# Schematic-final-Susai-Florian.net
KiCad netlist of a schematic drawn in EAGLE
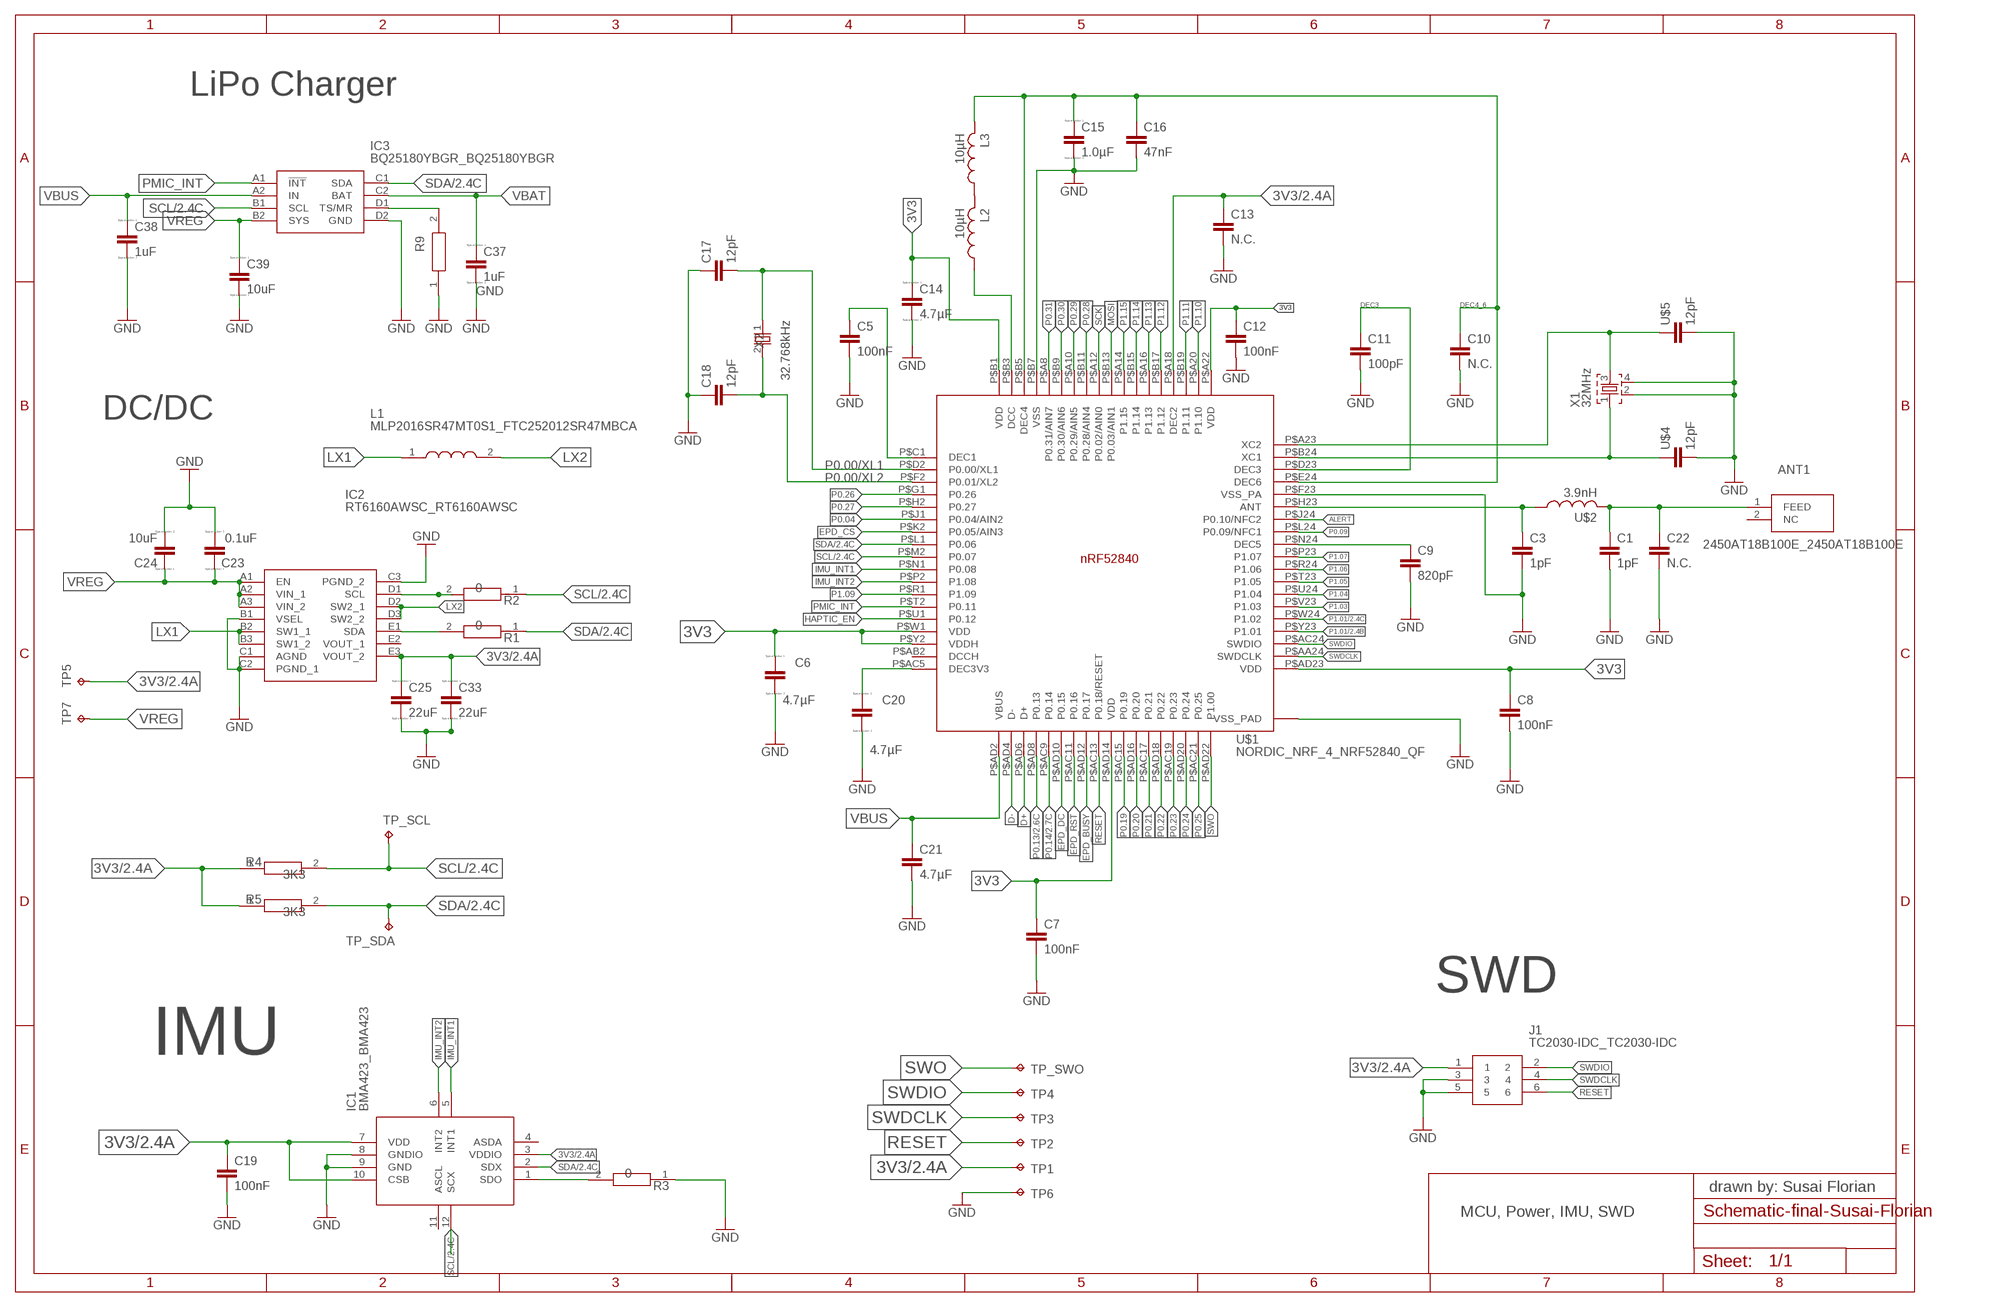
[diagram p0: schematic, sheet 1, part 1 of 2]
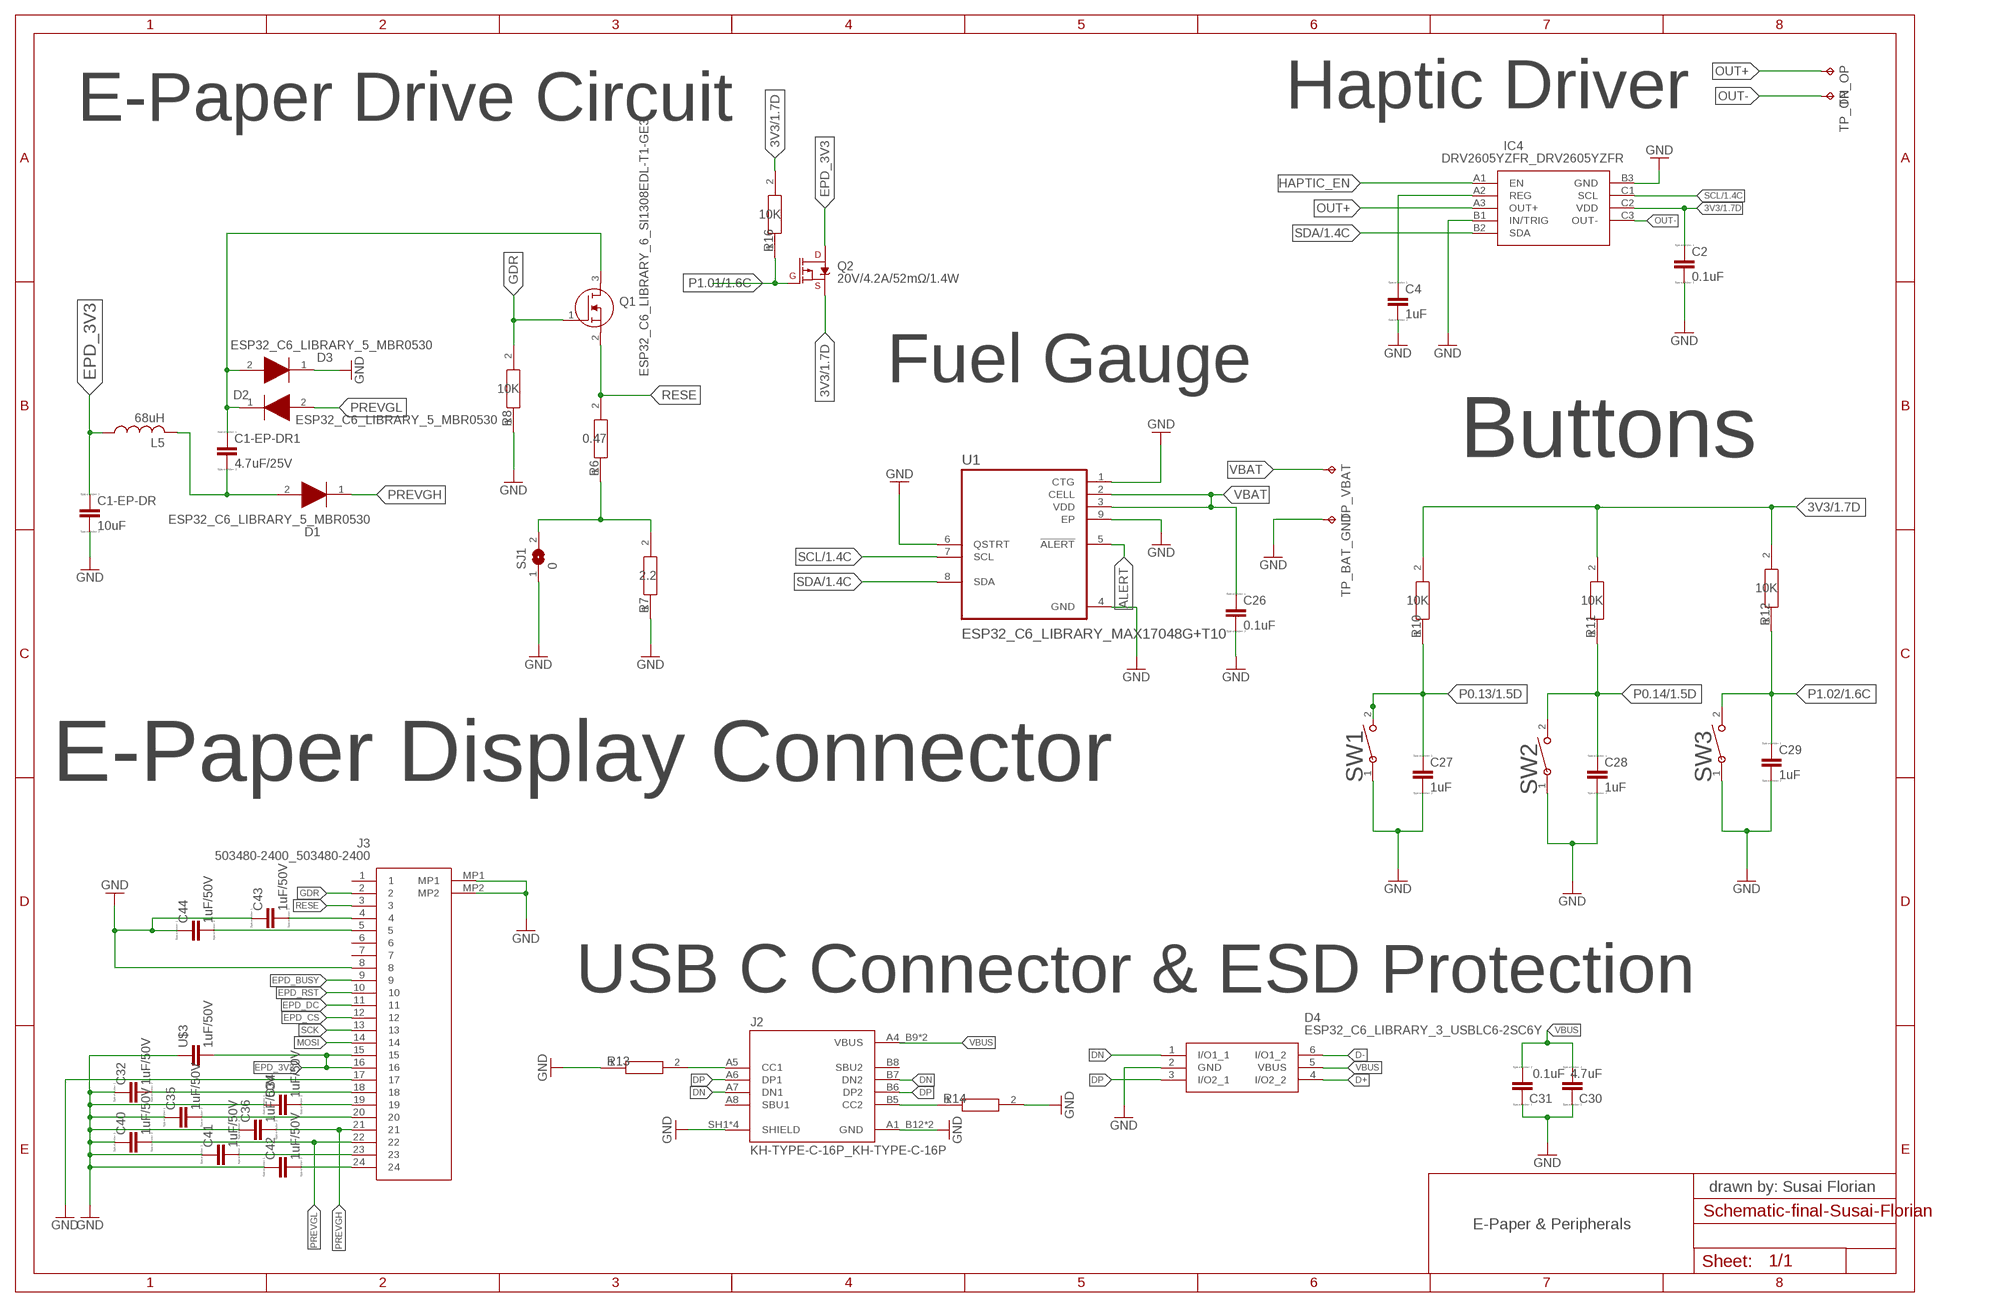
[diagram p1: schematic, sheet 1, part 2 of 2]

(export (version "E")
  (design (tool "Eeschema 10.0.6"))
  (components
    (comp (ref "ANT1")
      (value "2450AT18B100E_2450AT18B100E")
      (footprint "eagle-import:2450AT18B100E_ANTC3216X140N")
      (fields
        (field (name "ARROW_PART_NUMBER") "2450AT18B100E")
        (field (name "MOUSER_PART_NUMBER") "609-2450AT18B100E")
      )
      (libsource (lib "eagle-import") (part "2450AT18B100E_2450AT18B100E"))
    )
    (comp (ref "C1")
      (value "1pF")
      (footprint "eagle-import:NORDIC_NRF_3_RESC0201_L")
      (libsource (lib "eagle-import") (part "NORDIC_NRF_3_CAPACITOR_0201_L"))
    )
    (comp (ref "C1-EP-DR")
      (value "10uF")
      (footprint "eagle-import:ESP32_C6_LIBRARY_1_ESP32_WROVER_EAGLE-LTSPICE_C0402")
      (libsource (lib "eagle-import") (part "ESP32_C6_LIBRARY_1_ESP32_WROVER_EAGLE-LTSPICE_CC0402"))
    )
    (comp (ref "C1-EP-DR1")
      (value "4.7uF/25V")
      (footprint "eagle-import:ESP32_C6_LIBRARY_1_ESP32_WROVER_EAGLE-LTSPICE_C0402")
      (libsource (lib "eagle-import") (part "ESP32_C6_LIBRARY_1_ESP32_WROVER_EAGLE-LTSPICE_CC0402"))
    )
    (comp (ref "C2")
      (value "0.1uF")
      (footprint "eagle-import:ESP32_C6_LIBRARY_1_ESP32_WROVER_EAGLE-LTSPICE_C0402")
      (libsource (lib "eagle-import") (part "ESP32_C6_LIBRARY_1_ESP32_WROVER_EAGLE-LTSPICE_CC0402"))
    )
    (comp (ref "C3")
      (value "1pF")
      (footprint "eagle-import:NORDIC_NRF_3_RESC0201_L")
      (libsource (lib "eagle-import") (part "NORDIC_NRF_3_CAPACITOR_0201_L"))
    )
    (comp (ref "C4")
      (value "1uF")
      (footprint "eagle-import:ESP32_C6_LIBRARY_1_ESP32_WROVER_EAGLE-LTSPICE_C0402")
      (libsource (lib "eagle-import") (part "ESP32_C6_LIBRARY_1_ESP32_WROVER_EAGLE-LTSPICE_CC0402"))
    )
    (comp (ref "C5")
      (value "100nF")
      (footprint "eagle-import:NORDIC_NRF_3_RESC0201_L")
      (libsource (lib "eagle-import") (part "NORDIC_NRF_3_CAPACITOR_0201_L"))
    )
    (comp (ref "C6")
      (value "4.7µF")
      (footprint "eagle-import:ESP32_C6_LIBRARY_1_ESP32_WROVER_EAGLE-LTSPICE_C0402")
      (libsource (lib "eagle-import") (part "ESP32_C6_LIBRARY_1_ESP32_WROVER_EAGLE-LTSPICE_CC0402"))
    )
    (comp (ref "C7")
      (value "100nF")
      (footprint "eagle-import:NORDIC_NRF_3_RESC0201_L")
      (libsource (lib "eagle-import") (part "NORDIC_NRF_3_CAPACITOR_0201_L"))
    )
    (comp (ref "C8")
      (value "100nF")
      (footprint "eagle-import:NORDIC_NRF_3_RESC0201_L")
      (libsource (lib "eagle-import") (part "NORDIC_NRF_3_CAPACITOR_0201_L"))
    )
    (comp (ref "C9")
      (value "820pF")
      (footprint "eagle-import:NORDIC_NRF_3_RESC0201_L")
      (libsource (lib "eagle-import") (part "NORDIC_NRF_3_CAPACITOR_0201_L"))
    )
    (comp (ref "C10")
      (value "N.C.")
      (footprint "eagle-import:NORDIC_NRF_3_RESC0201_L")
      (libsource (lib "eagle-import") (part "NORDIC_NRF_3_CAPACITOR_0201_L"))
    )
    (comp (ref "C11")
      (value "100pF")
      (footprint "eagle-import:NORDIC_NRF_3_RESC0201_L")
      (libsource (lib "eagle-import") (part "NORDIC_NRF_3_CAPACITOR_0201_L"))
    )
    (comp (ref "C12")
      (value "100nF")
      (footprint "eagle-import:NORDIC_NRF_3_RESC0201_L")
      (libsource (lib "eagle-import") (part "NORDIC_NRF_3_CAPACITOR_0201_L"))
    )
    (comp (ref "C13")
      (value "N.C.")
      (footprint "eagle-import:NORDIC_NRF_3_RESC0201_L")
      (libsource (lib "eagle-import") (part "NORDIC_NRF_3_CAPACITOR_0201_L"))
    )
    (comp (ref "C14")
      (value "4.7µF")
      (footprint "eagle-import:ESP32_C6_LIBRARY_1_ESP32_WROVER_EAGLE-LTSPICE_C0402")
      (libsource (lib "eagle-import") (part "ESP32_C6_LIBRARY_1_ESP32_WROVER_EAGLE-LTSPICE_CC0402"))
    )
    (comp (ref "C15")
      (value "1.0µF")
      (footprint "eagle-import:ESP32_C6_LIBRARY_1_ESP32_WROVER_EAGLE-LTSPICE_C0402")
      (libsource (lib "eagle-import") (part "ESP32_C6_LIBRARY_1_ESP32_WROVER_EAGLE-LTSPICE_CC0402"))
    )
    (comp (ref "C16")
      (value "47nF")
      (footprint "eagle-import:NORDIC_NRF_3_RESC0201_L")
      (libsource (lib "eagle-import") (part "NORDIC_NRF_3_CAPACITOR_0201_L"))
    )
    (comp (ref "C17")
      (value "12pF")
      (footprint "eagle-import:NORDIC_NRF_3_RESC0201_L")
      (libsource (lib "eagle-import") (part "NORDIC_NRF_3_CAPACITOR_0201_L"))
    )
    (comp (ref "C18")
      (value "12pF")
      (footprint "eagle-import:NORDIC_NRF_3_RESC0201_L")
      (libsource (lib "eagle-import") (part "NORDIC_NRF_3_CAPACITOR_0201_L"))
    )
    (comp (ref "C19")
      (value "100nF")
      (footprint "eagle-import:NORDIC_NRF_3_RESC0201_L")
      (libsource (lib "eagle-import") (part "NORDIC_NRF_3_CAPACITOR_0201_L"))
    )
    (comp (ref "C20")
      (value "4.7µF")
      (footprint "eagle-import:ESP32_C6_LIBRARY_1_ESP32_WROVER_EAGLE-LTSPICE_C0402")
      (libsource (lib "eagle-import") (part "ESP32_C6_LIBRARY_1_ESP32_WROVER_EAGLE-LTSPICE_CC0402"))
    )
    (comp (ref "C21")
      (value "4.7µF")
      (footprint "eagle-import:NORDIC_NRF_3_RESC0402_L")
      (libsource (lib "eagle-import") (part "NORDIC_NRF_3_CAPACITOR_0402_L"))
    )
    (comp (ref "C22")
      (value "N.C.")
      (footprint "eagle-import:NORDIC_NRF_3_RESC0201_L")
      (libsource (lib "eagle-import") (part "NORDIC_NRF_3_CAPACITOR_0201_L"))
    )
    (comp (ref "C23")
      (value "0.1uF")
      (footprint "eagle-import:ESP32_C6_LIBRARY_1_ESP32_WROVER_EAGLE-LTSPICE_C0402")
      (libsource (lib "eagle-import") (part "ESP32_C6_LIBRARY_1_ESP32_WROVER_EAGLE-LTSPICE_CC0402"))
    )
    (comp (ref "C24")
      (value "10uF")
      (footprint "eagle-import:ESP32_C6_LIBRARY_1_ESP32_WROVER_EAGLE-LTSPICE_C0402")
      (libsource (lib "eagle-import") (part "ESP32_C6_LIBRARY_1_ESP32_WROVER_EAGLE-LTSPICE_CC0402"))
    )
    (comp (ref "C25")
      (value "22uF")
      (footprint "eagle-import:ESP32_C6_LIBRARY_1_ESP32_WROVER_EAGLE-LTSPICE_C0402")
      (libsource (lib "eagle-import") (part "ESP32_C6_LIBRARY_1_ESP32_WROVER_EAGLE-LTSPICE_CC0402"))
    )
    (comp (ref "C26")
      (value "0.1uF")
      (footprint "eagle-import:ESP32_C6_LIBRARY_1_ESP32_WROVER_EAGLE-LTSPICE_C0402")
      (libsource (lib "eagle-import") (part "ESP32_C6_LIBRARY_1_ESP32_WROVER_EAGLE-LTSPICE_CC0402"))
    )
    (comp (ref "C27")
      (value "1uF")
      (footprint "eagle-import:ESP32_C6_LIBRARY_1_ESP32_WROVER_EAGLE-LTSPICE_C0402")
      (libsource (lib "eagle-import") (part "ESP32_C6_LIBRARY_1_ESP32_WROVER_EAGLE-LTSPICE_CC0402"))
    )
    (comp (ref "C28")
      (value "1uF")
      (footprint "eagle-import:ESP32_C6_LIBRARY_1_ESP32_WROVER_EAGLE-LTSPICE_C0402")
      (libsource (lib "eagle-import") (part "ESP32_C6_LIBRARY_1_ESP32_WROVER_EAGLE-LTSPICE_CC0402"))
    )
    (comp (ref "C29")
      (value "1uF")
      (footprint "eagle-import:ESP32_C6_LIBRARY_1_ESP32_WROVER_EAGLE-LTSPICE_C0402")
      (libsource (lib "eagle-import") (part "ESP32_C6_LIBRARY_1_ESP32_WROVER_EAGLE-LTSPICE_CC0402"))
    )
    (comp (ref "C30")
      (value "4.7uF")
      (footprint "eagle-import:ESP32_C6_LIBRARY_1_ESP32_WROVER_EAGLE-LTSPICE_C0402")
      (libsource (lib "eagle-import") (part "ESP32_C6_LIBRARY_1_ESP32_WROVER_EAGLE-LTSPICE_CC0402"))
    )
    (comp (ref "C31")
      (value "0.1uF")
      (footprint "eagle-import:ESP32_C6_LIBRARY_1_ESP32_WROVER_EAGLE-LTSPICE_C0402")
      (libsource (lib "eagle-import") (part "ESP32_C6_LIBRARY_1_ESP32_WROVER_EAGLE-LTSPICE_CC0402"))
    )
    (comp (ref "C32")
      (value "1uF/50V")
      (footprint "eagle-import:ESP32_C6_LIBRARY_1_ESP32_WROVER_EAGLE-LTSPICE_C0402")
      (libsource (lib "eagle-import") (part "ESP32_C6_LIBRARY_1_ESP32_WROVER_EAGLE-LTSPICE_CC0402"))
    )
    (comp (ref "C33")
      (value "22uF")
      (footprint "eagle-import:ESP32_C6_LIBRARY_1_ESP32_WROVER_EAGLE-LTSPICE_C0402")
      (libsource (lib "eagle-import") (part "ESP32_C6_LIBRARY_1_ESP32_WROVER_EAGLE-LTSPICE_CC0402"))
    )
    (comp (ref "C34")
      (value "1uF/50V")
      (footprint "eagle-import:ESP32_C6_LIBRARY_1_ESP32_WROVER_EAGLE-LTSPICE_C0402")
      (libsource (lib "eagle-import") (part "ESP32_C6_LIBRARY_1_ESP32_WROVER_EAGLE-LTSPICE_CC0402"))
    )
    (comp (ref "C35")
      (value "1uF/50V")
      (footprint "eagle-import:ESP32_C6_LIBRARY_1_ESP32_WROVER_EAGLE-LTSPICE_C0402")
      (libsource (lib "eagle-import") (part "ESP32_C6_LIBRARY_1_ESP32_WROVER_EAGLE-LTSPICE_CC0402"))
    )
    (comp (ref "C36")
      (value "1uF/50V")
      (footprint "eagle-import:ESP32_C6_LIBRARY_1_ESP32_WROVER_EAGLE-LTSPICE_C0402")
      (libsource (lib "eagle-import") (part "ESP32_C6_LIBRARY_1_ESP32_WROVER_EAGLE-LTSPICE_CC0402"))
    )
    (comp (ref "C37")
      (value "1uF")
      (footprint "eagle-import:ESP32_C6_LIBRARY_1_ESP32_WROVER_EAGLE-LTSPICE_C0402")
      (libsource (lib "eagle-import") (part "ESP32_C6_LIBRARY_1_ESP32_WROVER_EAGLE-LTSPICE_CC0402"))
    )
    (comp (ref "C38")
      (value "1uF")
      (footprint "eagle-import:ESP32_C6_LIBRARY_1_ESP32_WROVER_EAGLE-LTSPICE_C0402")
      (libsource (lib "eagle-import") (part "ESP32_C6_LIBRARY_1_ESP32_WROVER_EAGLE-LTSPICE_CC0402"))
    )
    (comp (ref "C39")
      (value "10uF")
      (footprint "eagle-import:ESP32_C6_LIBRARY_1_ESP32_WROVER_EAGLE-LTSPICE_C0402")
      (libsource (lib "eagle-import") (part "ESP32_C6_LIBRARY_1_ESP32_WROVER_EAGLE-LTSPICE_CC0402"))
    )
    (comp (ref "C40")
      (value "1uF/50V")
      (footprint "eagle-import:ESP32_C6_LIBRARY_1_ESP32_WROVER_EAGLE-LTSPICE_C0402")
      (libsource (lib "eagle-import") (part "ESP32_C6_LIBRARY_1_ESP32_WROVER_EAGLE-LTSPICE_CC0402"))
    )
    (comp (ref "C41")
      (value "1uF/50V")
      (footprint "eagle-import:ESP32_C6_LIBRARY_1_ESP32_WROVER_EAGLE-LTSPICE_C0402")
      (libsource (lib "eagle-import") (part "ESP32_C6_LIBRARY_1_ESP32_WROVER_EAGLE-LTSPICE_CC0402"))
    )
    (comp (ref "C42")
      (value "1uF/50V")
      (footprint "eagle-import:ESP32_C6_LIBRARY_1_ESP32_WROVER_EAGLE-LTSPICE_C0402")
      (libsource (lib "eagle-import") (part "ESP32_C6_LIBRARY_1_ESP32_WROVER_EAGLE-LTSPICE_CC0402"))
    )
    (comp (ref "C43")
      (value "1uF/50V")
      (footprint "eagle-import:ESP32_C6_LIBRARY_1_ESP32_WROVER_EAGLE-LTSPICE_C0402")
      (libsource (lib "eagle-import") (part "ESP32_C6_LIBRARY_1_ESP32_WROVER_EAGLE-LTSPICE_CC0402"))
    )
    (comp (ref "C44")
      (value "1uF/50V")
      (footprint "eagle-import:ESP32_C6_LIBRARY_1_ESP32_WROVER_EAGLE-LTSPICE_C0402")
      (libsource (lib "eagle-import") (part "ESP32_C6_LIBRARY_1_ESP32_WROVER_EAGLE-LTSPICE_CC0402"))
    )
    (comp (ref "D1")
      (value "ESP32_C6_LIBRARY_5_MBR0530")
      (footprint "eagle-import:ESP32_C6_LIBRARY_5_SOD3716X135N")
      (fields (field (name "MF") "ON Semiconductor") (field (name "MP") "MBR0530"))
      (libsource (lib "eagle-import") (part "ESP32_C6_LIBRARY_5_MBR0530"))
    )
    (comp (ref "D2")
      (value "ESP32_C6_LIBRARY_5_MBR0530")
      (footprint "eagle-import:ESP32_C6_LIBRARY_5_SOD3716X135N")
      (fields (field (name "MF") "ON Semiconductor") (field (name "MP") "MBR0530"))
      (libsource (lib "eagle-import") (part "ESP32_C6_LIBRARY_5_MBR0530"))
    )
    (comp (ref "D3")
      (value "ESP32_C6_LIBRARY_5_MBR0530")
      (footprint "eagle-import:ESP32_C6_LIBRARY_5_SOD3716X135N")
      (fields (field (name "MF") "ON Semiconductor") (field (name "MP") "MBR0530"))
      (libsource (lib "eagle-import") (part "ESP32_C6_LIBRARY_5_MBR0530"))
    )
    (comp (ref "D4")
      (value "ESP32_C6_LIBRARY_3_USBLC6-2SC6Y")
      (footprint "eagle-import:ESP32_C6_LIBRARY_3_SOT95P280X145-6N")
      (fields (field (name "MF") "STMicroelectronics") (field (name "MP") "USBLC6-2SC6Y"))
      (libsource (lib "eagle-import") (part "ESP32_C6_LIBRARY_3_USBLC6-2SC6Y"))
    )
    (comp (ref "IC1")
      (value "BMA423_BMA423")
      (footprint "eagle-import:BMA423_BMA423")
      (fields (field (name "ARROW_PART_NUMBER") "BMA423") (field (name "MOUSER_PART_NUMBER") "262-BMA423"))
      (libsource (lib "eagle-import") (part "BMA423_BMA423"))
    )
    (comp (ref "IC2")
      (value "RT6160AWSC_RT6160AWSC")
      (footprint "eagle-import:RT6160AWSC_BGA15C40P3X5_140X230X60")
      (fields
        (field (name "MANUFACTURER_PART_NUMBER") "RT6160AWSC")
        (field (name "MOUSER_PART_NUMBER") "835-RT6160AWSC")
      )
      (libsource (lib "eagle-import") (part "RT6160AWSC_RT6160AWSC"))
    )
    (comp (ref "IC3")
      (value "BQ25180YBGR_BQ25180YBGR")
      (footprint "eagle-import:BQ25180YBGR_BGA8C40P2X4_100X155X50")
      (fields
        (field (name "ARROW_PART_NUMBER") "BQ25180YBGR")
        (field (name "MOUSER_PART_NUMBER") "595-BQ25180YBGR")
      )
      (libsource (lib "eagle-import") (part "BQ25180YBGR_BQ25180YBGR"))
    )
    (comp (ref "IC4")
      (value "DRV2605YZFR_DRV2605YZFR")
      (footprint "eagle-import:DRV2605YZFR_BGA9C50P3X3_144X144X62")
      (fields (field (name "ARROW_PART_NUMBER") "DRV2605YZFR"))
      (libsource (lib "eagle-import") (part "DRV2605YZFR_DRV2605YZFR"))
    )
    (comp (ref "J1")
      (value "TC2030-IDC_TC2030-IDC")
      (footprint "eagle-import:TC2030-IDC_TC2030IDC")
      (fields (field (name "MANUFACTURER_PART_NUMBER") "TC2030-IDC"))
      (libsource (lib "eagle-import") (part "TC2030-IDC_TC2030-IDC"))
    )
    (comp (ref "J2")
      (value "KH-TYPE-C-16P_KH-TYPE-C-16P")
      (footprint "eagle-import:KH-TYPE-C-16P_KINGHELM_KH-TYPE-C-16P")
      (fields (field (name "MF") "kinghelm") (field (name "MP") "KH-TYPE-C-16P"))
      (libsource (lib "eagle-import") (part "KH-TYPE-C-16P_KH-TYPE-C-16P"))
    )
    (comp (ref "J3")
      (value "503480-2400_503480-2400")
      (footprint "eagle-import:503480-2400_5034802400")
      (fields
        (field (name "MANUFACTURER_PART_NUMBER") "503480-2400")
        (field (name "MOUSER_PART_NUMBER") "538-503480-2400")
      )
      (libsource (lib "eagle-import") (part "503480-2400_503480-2400"))
    )
    (comp (ref "L1")
      (value "MLP2016SR47MT0S1_FTC252012SR47MBCA")
      (footprint "eagle-import:MLP2016SR47MT0S1_INDC2016X100N")
      (fields (field (name "MANUFACTURER_PART_NUMBER") "FTC252012SR47MBCA"))
      (libsource (lib "eagle-import") (part "MLP2016SR47MT0S1_FTC252012SR47MBCA"))
    )
    (comp (ref "L2")
      (value "10µH")
      (footprint "eagle-import:NORDIC_NRF_2_RESC0402_L")
      (libsource (lib "eagle-import") (part "NORDIC_NRF_2_INDUCTOR_0402_L"))
    )
    (comp (ref "L3")
      (value "10µH")
      (footprint "eagle-import:NORDIC_NRF_2_RESC0402_L")
      (libsource (lib "eagle-import") (part "NORDIC_NRF_2_INDUCTOR_0402_L"))
    )
    (comp (ref "L5")
      (value "68uH")
      (footprint "eagle-import:NORDIC_NRF_2_RESC0201_L")
      (libsource (lib "eagle-import") (part "NORDIC_NRF_2_INDUCTOR_0201_L"))
    )
    (comp (ref "Q1")
      (value "ESP32_C6_LIBRARY_6_SI1308EDL-T1-GE3")
      (footprint "eagle-import:ESP32_C6_LIBRARY_6_SOT65P210X110-3N")
      (fields (field (name "MF") "Vishay Siliconix") (field (name "MP") "SI1308EDL-T1-GE3"))
      (libsource (lib "eagle-import") (part "ESP32_C6_LIBRARY_6_SI1308EDL-T1-GE3"))
    )
    (comp (ref "Q2")
      (value "20V/4.2A/52mΩ/1.4W")
      (footprint "eagle-import:ESP32_C6_LIBRARY_4_ESP32_C6_LIBRARY_4_ESP32_C6_LIBRARY_4_ESP32_C6_LIBRARY_4_ESP32_WROVER_SPARKFUN-DISCRETESEMI_SOT23-3")
      (libsource (lib "eagle-import") (part "ESP32_C6_LIBRARY_4_ESP32_WROVER_SPARKFUN-DISCRETESEMI_MOSFET_PCH-DMG2305UX-7"))
    )
    (comp (ref "R1")
      (value "0")
      (footprint "eagle-import:CPF0201D7K68C1_0201")
      (libsource (lib "eagle-import") (part "CPF0201D7K68C1_CPF0201D7K68C1"))
    )
    (comp (ref "R2")
      (value "0")
      (footprint "eagle-import:CPF0201D7K68C1_0201")
      (libsource (lib "eagle-import") (part "CPF0201D7K68C1_CPF0201D7K68C1"))
    )
    (comp (ref "R3")
      (value "0")
      (footprint "eagle-import:CPF0201D7K68C1_0201")
      (libsource (lib "eagle-import") (part "CPF0201D7K68C1_CPF0201D7K68C1"))
    )
    (comp (ref "R4")
      (value "3K3")
      (footprint "eagle-import:CPF0201D7K68C1_0201")
      (libsource (lib "eagle-import") (part "CPF0201D7K68C1_CPF0201D7K68C1"))
    )
    (comp (ref "R5")
      (value "3K3")
      (footprint "eagle-import:CPF0201D7K68C1_0201")
      (libsource (lib "eagle-import") (part "CPF0201D7K68C1_CPF0201D7K68C1"))
    )
    (comp (ref "R6")
      (value "0.47")
      (footprint "eagle-import:CPF0201D7K68C1_0201")
      (libsource (lib "eagle-import") (part "CPF0201D7K68C1_CPF0201D7K68C1"))
    )
    (comp (ref "R7")
      (value "2.2")
      (footprint "eagle-import:CPF0201D7K68C1_0201")
      (libsource (lib "eagle-import") (part "CPF0201D7K68C1_CPF0201D7K68C1"))
    )
    (comp (ref "R8")
      (value "10K")
      (footprint "eagle-import:CPF0201D7K68C1_0201")
      (libsource (lib "eagle-import") (part "CPF0201D7K68C1_CPF0201D7K68C1"))
    )
    (comp (ref "R9")
      (value "10K")
      (footprint "eagle-import:CPF0201D7K68C1_0201")
      (libsource (lib "eagle-import") (part "CPF0201D7K68C1_CPF0201D7K68C1"))
    )
    (comp (ref "R10")
      (value "10K")
      (footprint "eagle-import:CPF0201D7K68C1_0201")
      (libsource (lib "eagle-import") (part "CPF0201D7K68C1_CPF0201D7K68C1"))
    )
    (comp (ref "R11")
      (value "10K")
      (footprint "eagle-import:CPF0201D7K68C1_0201")
      (libsource (lib "eagle-import") (part "CPF0201D7K68C1_CPF0201D7K68C1"))
    )
    (comp (ref "R12")
      (value "10K")
      (footprint "eagle-import:CPF0201D7K68C1_0201")
      (libsource (lib "eagle-import") (part "CPF0201D7K68C1_CPF0201D7K68C1"))
    )
    (comp (ref "R13")
      (value "10K")
      (footprint "eagle-import:CPF0201D7K68C1_0201")
      (libsource (lib "eagle-import") (part "CPF0201D7K68C1_CPF0201D7K68C1"))
    )
    (comp (ref "R14")
      (value "10K")
      (footprint "eagle-import:CPF0201D7K68C1_0201")
      (libsource (lib "eagle-import") (part "CPF0201D7K68C1_CPF0201D7K68C1"))
    )
    (comp (ref "R16")
      (value "10K")
      (footprint "eagle-import:CPF0201D7K68C1_0201")
      (libsource (lib "eagle-import") (part "CPF0201D7K68C1_CPF0201D7K68C1"))
    )
    (comp (ref "SJ1")
      (value "0")
      (footprint "eagle-import:ESP32_C6_LIBRARY_7_JUMPER_SJ")
      (libsource (lib "eagle-import") (part "ESP32_C6_LIBRARY_7_JUMPER_SJ"))
    )
    (comp (ref "SW1")
      (value "2025-10-22_07-23-44_LIBRARY_EVP-AKE31ASW_EVP-AKE31A_PAN")
      (footprint "eagle-import:2025-10-22_07-23-44_LIBRARY_SW_EVP-AKE31A_PAN")
      (fields
        (field (name "MANUFACTURER_PART_NUMBER") "EVP-AKE31A")
        (field (name "COPYRIGHT") "Copyright (C) 2025 Ultra Librarian. All rights reserved.")
      )
      (libsource (lib "eagle-import") (part "2025-10-22_07-23-44_LIBRARY_EVP-AKE31ASW_EVP-AKE31A_PAN"))
    )
    (comp (ref "SW2")
      (value "2025-10-22_07-23-44_LIBRARY_EVP-AKE31ASW_EVP-AKE31A_PAN")
      (footprint "eagle-import:2025-10-22_07-23-44_LIBRARY_SW_EVP-AKE31A_PAN")
      (fields
        (field (name "MANUFACTURER_PART_NUMBER") "EVP-AKE31A")
        (field (name "COPYRIGHT") "Copyright (C) 2025 Ultra Librarian. All rights reserved.")
      )
      (libsource (lib "eagle-import") (part "2025-10-22_07-23-44_LIBRARY_EVP-AKE31ASW_EVP-AKE31A_PAN"))
    )
    (comp (ref "SW3")
      (value "2025-10-22_07-23-44_LIBRARY_EVP-AKE31ASW_EVP-AKE31A_PAN")
      (footprint "eagle-import:2025-10-22_07-23-44_LIBRARY_SW_EVP-AKE31A_PAN")
      (fields
        (field (name "MANUFACTURER_PART_NUMBER") "EVP-AKE31A")
        (field (name "COPYRIGHT") "Copyright (C) 2025 Ultra Librarian. All rights reserved.")
      )
      (libsource (lib "eagle-import") (part "2025-10-22_07-23-44_LIBRARY_EVP-AKE31ASW_EVP-AKE31A_PAN"))
    )
    (comp (ref "TP1")
      (value "HECTOR_WATCH_1_TPTP20R")
      (footprint "eagle-import:HECTOR_WATCH_1_TP20R")
      (libsource (lib "eagle-import") (part "HECTOR_WATCH_1_TPTP20R"))
    )
    (comp (ref "TP2")
      (value "HECTOR_WATCH_1_TPTP20R")
      (footprint "eagle-import:HECTOR_WATCH_1_TP20R")
      (libsource (lib "eagle-import") (part "HECTOR_WATCH_1_TPTP20R"))
    )
    (comp (ref "TP3")
      (value "HECTOR_WATCH_1_TPTP20R")
      (footprint "eagle-import:HECTOR_WATCH_1_TP20R")
      (libsource (lib "eagle-import") (part "HECTOR_WATCH_1_TPTP20R"))
    )
    (comp (ref "TP4")
      (value "HECTOR_WATCH_1_TPTP20R")
      (footprint "eagle-import:HECTOR_WATCH_1_TP20R")
      (libsource (lib "eagle-import") (part "HECTOR_WATCH_1_TPTP20R"))
    )
    (comp (ref "TP5")
      (value "HECTOR_WATCH_1_TPTP20R")
      (footprint "eagle-import:HECTOR_WATCH_1_TP20R")
      (libsource (lib "eagle-import") (part "HECTOR_WATCH_1_TPTP20R"))
    )
    (comp (ref "TP6")
      (value "HECTOR_WATCH_1_TPTP20R")
      (footprint "eagle-import:HECTOR_WATCH_1_TP20R")
      (libsource (lib "eagle-import") (part "HECTOR_WATCH_1_TPTP20R"))
    )
    (comp (ref "TP7")
      (value "HECTOR_WATCH_1_TPTP20R")
      (footprint "eagle-import:HECTOR_WATCH_1_TP20R")
      (libsource (lib "eagle-import") (part "HECTOR_WATCH_1_TPTP20R"))
    )
    (comp (ref "TP_BAT_GND")
      (value "HECTOR_WATCH_1_TPTP20R")
      (footprint "eagle-import:HECTOR_WATCH_1_TP20R")
      (libsource (lib "eagle-import") (part "HECTOR_WATCH_1_TPTP20R"))
    )
    (comp (ref "TP_ON")
      (value "HECTOR_WATCH_1_TPTP20R")
      (footprint "eagle-import:HECTOR_WATCH_1_TP20R")
      (libsource (lib "eagle-import") (part "HECTOR_WATCH_1_TPTP20R"))
    )
    (comp (ref "TP_OP")
      (value "HECTOR_WATCH_1_TPTP20R")
      (footprint "eagle-import:HECTOR_WATCH_1_TP20R")
      (libsource (lib "eagle-import") (part "HECTOR_WATCH_1_TPTP20R"))
    )
    (comp (ref "TP_SCL")
      (value "HECTOR_WATCH_1_TPTP20R")
      (footprint "eagle-import:HECTOR_WATCH_1_TP20R")
      (libsource (lib "eagle-import") (part "HECTOR_WATCH_1_TPTP20R"))
    )
    (comp (ref "TP_SDA")
      (value "HECTOR_WATCH_1_TPTP20R")
      (footprint "eagle-import:HECTOR_WATCH_1_TP20R")
      (libsource (lib "eagle-import") (part "HECTOR_WATCH_1_TPTP20R"))
    )
    (comp (ref "TP_SWO")
      (value "HECTOR_WATCH_1_TPTP20R")
      (footprint "eagle-import:HECTOR_WATCH_1_TP20R")
      (libsource (lib "eagle-import") (part "HECTOR_WATCH_1_TPTP20R"))
    )
    (comp (ref "TP_VBAT")
      (value "HECTOR_WATCH_1_TPTP20R")
      (footprint "eagle-import:HECTOR_WATCH_1_TP20R")
      (libsource (lib "eagle-import") (part "HECTOR_WATCH_1_TPTP20R"))
    )
    (comp (ref "U$1")
      (value "NORDIC_NRF_4_NRF52840_QF")
      (footprint "eagle-import:NORDIC_NRF_4_AQFN50P700X700X85_HS-74N")
      (libsource (lib "eagle-import") (part "NORDIC_NRF_4_NRF52840_QF"))
    )
    (comp (ref "U$2")
      (value "3.9nH")
      (footprint "eagle-import:NORDIC_NRF_2_RESC0402_L")
      (libsource (lib "eagle-import") (part "NORDIC_NRF_2_INDUCTOR_0402_L"))
    )
    (comp (ref "U$3")
      (value "1uF/50V")
      (footprint "eagle-import:NORDIC_NRF_3_RESC0201_L")
      (libsource (lib "eagle-import") (part "NORDIC_NRF_3_CAPACITOR_0201_L"))
    )
    (comp (ref "U$4")
      (value "12pF")
      (footprint "eagle-import:NORDIC_NRF_3_RESC0201_L")
      (libsource (lib "eagle-import") (part "NORDIC_NRF_3_CAPACITOR_0201_L"))
    )
    (comp (ref "U$5")
      (value "12pF")
      (footprint "eagle-import:NORDIC_NRF_3_RESC0201_L")
      (libsource (lib "eagle-import") (part "NORDIC_NRF_3_CAPACITOR_0201_L"))
    )
    (comp (ref "U1")
      (value "ESP32_C6_LIBRARY_MAX17048G+T10")
      (footprint "eagle-import:ESP32_C6_LIBRARY_SON50P200X200X80-9N")
      (fields (field (name "MF") "Analog Devices") (field (name "MP") "MAX17048G+T10"))
      (libsource (lib "eagle-import") (part "ESP32_C6_LIBRARY_MAX17048G+T10"))
    )
    (comp (ref "X1")
      (value "32MHz")
      (footprint "eagle-import:NORDIC_NRF_BT-XTAL_2016_N")
      (libsource (lib "eagle-import") (part "NORDIC_NRF_XTAL_32MHZ"))
    )
    (comp (ref "X2")
      (value "32.768kHz")
      (footprint "eagle-import:NORDIC_NRF_1_XTAL_3215_N")
      (libsource (lib "eagle-import") (part "NORDIC_NRF_1_XTAL_32KHZ"))
    )
  )
  (nets
    (net (code "1") (name "/DEC3") (class "Default")
      (node (ref "C11") (pin "1") (pinfunction "1_1") (pintype "passive"))
      (node (ref "U$1") (pin "P$D23") (pinfunction "DEC3_P$D23") (pintype "bidirectional"))
    )
    (net (code "2") (name "/DEC4_6") (class "Default")
      (node (ref "C10") (pin "1") (pinfunction "1_1") (pintype "passive"))
      (node (ref "C15") (pin "1") (pinfunction "1_1") (pintype "passive"))
      (node (ref "C16") (pin "1") (pinfunction "1_1") (pintype "passive"))
      (node (ref "L3") (pin "2") (pinfunction "2_2") (pintype "passive"))
      (node (ref "U$1") (pin "P$B5") (pinfunction "DEC4_P$B5") (pintype "power_in"))
      (node (ref "U$1") (pin "P$E24") (pinfunction "DEC6_P$E24") (pintype "bidirectional"))
    )
    (net (code "3") (name "/P0.00{slash}XL1") (class "Default")
      (node (ref "C17") (pin "2") (pinfunction "2_2") (pintype "passive"))
      (node (ref "U$1") (pin "P$D2") (pinfunction "P0.00/XL1_P$D2") (pintype "bidirectional"))
      (node (ref "X2") (pin "1") (pinfunction "1_1") (pintype "passive"))
    )
    (net (code "4") (name "/P0.00{slash}XL2") (class "Default")
      (node (ref "C18") (pin "2") (pinfunction "2_2") (pintype "passive"))
      (node (ref "U$1") (pin "P$F2") (pinfunction "P0.01/XL2_P$F2") (pintype "bidirectional"))
      (node (ref "X2") (pin "2") (pinfunction "2_2") (pintype "passive"))
    )
    (net (code "5") (name "3V3") (class "Default")
      (node (ref "C12") (pin "1") (pinfunction "1_1") (pintype "passive"))
      (node (ref "C14") (pin "1") (pinfunction "1_1") (pintype "passive"))
      (node (ref "C6") (pin "1") (pinfunction "1_1") (pintype "passive"))
      (node (ref "C7") (pin "1") (pinfunction "1_1") (pintype "passive"))
      (node (ref "C8") (pin "1") (pinfunction "1_1") (pintype "passive"))
      (node (ref "U$1") (pin "P$A22") (pinfunction "VDD_P$A22") (pintype "power_in"))
      (node (ref "U$1") (pin "P$AD14") (pinfunction "VDD_P$AD14") (pintype "power_in"))
      (node (ref "U$1") (pin "P$AD23") (pinfunction "VDD_P$AD23") (pintype "power_in"))
      (node (ref "U$1") (pin "P$B1") (pinfunction "VDD_P$B1") (pintype "power_in"))
      (node (ref "U$1") (pin "P$W1") (pinfunction "VDD_P$W1") (pintype "power_in"))
      (node (ref "U$1") (pin "P$Y2") (pinfunction "VDDH_P$Y2") (pintype "power_in"))
    )
    (net (code "6") (name "3V3{slash}1.7D") (class "Default")
      (node (ref "C2") (pin "1") (pinfunction "1_1") (pintype "passive"))
      (node (ref "IC4") (pin "C2") (pinfunction "VDD_C2") (pintype "bidirectional"))
      (node (ref "Q2") (pin "2") (pinfunction "S_2") (pintype "bidirectional"))
      (node (ref "R10") (pin "2") (pinfunction "2_2") (pintype "bidirectional"))
      (node (ref "R11") (pin "2") (pinfunction "2_2") (pintype "bidirectional"))
      (node (ref "R12") (pin "2") (pinfunction "2_2") (pintype "bidirectional"))
      (node (ref "R16") (pin "2") (pinfunction "2_2") (pintype "bidirectional"))
    )
    (net (code "7") (name "3V3{slash}2.4A") (class "Default")
      (node (ref "C13") (pin "1") (pinfunction "1_1") (pintype "passive"))
      (node (ref "C19") (pin "1") (pinfunction "1_1") (pintype "passive"))
      (node (ref "C25") (pin "1") (pinfunction "1_1") (pintype "passive"))
      (node (ref "C33") (pin "1") (pinfunction "1_1") (pintype "passive"))
      (node (ref "IC1") (pin "10") (pinfunction "CSB_10") (pintype "bidirectional"))
      (node (ref "IC1") (pin "3") (pinfunction "VDDIO_3") (pintype "bidirectional"))
      (node (ref "IC1") (pin "7") (pinfunction "VDD_7") (pintype "bidirectional"))
      (node (ref "IC2") (pin "E3") (pinfunction "VOUT_2_E3") (pintype "bidirectional"))
      (node (ref "J1") (pin "1") (pinfunction "1_1") (pintype "bidirectional"))
      (node (ref "R4") (pin "1") (pinfunction "1_1") (pintype "bidirectional"))
      (node (ref "R5") (pin "1") (pinfunction "1_1") (pintype "bidirectional"))
      (node (ref "TP1") (pin "TP") (pinfunction "TP_TP") (pintype "input"))
      (node (ref "TP5") (pin "TP") (pinfunction "TP_TP") (pintype "input"))
      (node (ref "U$1") (pin "P$A18") (pinfunction "DEC2_P$A18") (pintype "bidirectional"))
    )
    (net (code "8") (name "ALERT") (class "Default")
      (node (ref "U$1") (pin "P$J24") (pinfunction "P0.10/NFC2_P$J24") (pintype "bidirectional"))
      (node (ref "U1") (pin "5") (pinfunction "~{ALERT}_5") (pintype "output"))
    )
    (net (code "9") (name "D+") (class "Default")
      (node (ref "D4") (pin "4") (pinfunction "I/O2_2_4") (pintype "bidirectional"))
      (node (ref "U$1") (pin "P$AD6") (pinfunction "D+_P$AD6") (pintype "bidirectional"))
    )
    (net (code "10") (name "D-") (class "Default")
      (node (ref "D4") (pin "6") (pinfunction "I/O1_2_6") (pintype "bidirectional"))
      (node (ref "U$1") (pin "P$AD4") (pinfunction "D-_P$AD4") (pintype "bidirectional"))
    )
    (net (code "11") (name "DN") (class "Default")
      (node (ref "D4") (pin "1") (pinfunction "I/O1_1_1") (pintype "bidirectional"))
      (node (ref "J2") (pin "A7") (pinfunction "DN1_A7") (pintype "bidirectional"))
      (node (ref "J2") (pin "B7") (pinfunction "DN2_B7") (pintype "bidirectional"))
    )
    (net (code "12") (name "DP") (class "Default")
      (node (ref "D4") (pin "3") (pinfunction "I/O2_1_3") (pintype "bidirectional"))
      (node (ref "J2") (pin "A6") (pinfunction "DP1_A6") (pintype "bidirectional"))
      (node (ref "J2") (pin "B6") (pinfunction "DP2_B6") (pintype "bidirectional"))
    )
    (net (code "13") (name "EPD_3V3") (class "Default")
      (node (ref "C1-EP-DR") (pin "1") (pinfunction "1_1") (pintype "passive"))
      (node (ref "J3") (pin "15") (pinfunction "15_15") (pintype "bidirectional"))
      (node (ref "J3") (pin "16") (pinfunction "16_16") (pintype "bidirectional"))
      (node (ref "L5") (pin "1") (pinfunction "1_1") (pintype "passive"))
      (node (ref "Q2") (pin "3") (pinfunction "D_3") (pintype "bidirectional"))
      (node (ref "U$3") (pin "2") (pinfunction "2_2") (pintype "passive"))
    )
    (net (code "14") (name "EPD_BUSY") (class "Default")
      (node (ref "J3") (pin "9") (pinfunction "9_9") (pintype "bidirectional"))
      (node (ref "U$1") (pin "P$AD12") (pinfunction "P0.17_P$AD12") (pintype "bidirectional"))
    )
    (net (code "15") (name "EPD_CS") (class "Default")
      (node (ref "J3") (pin "12") (pinfunction "12_12") (pintype "bidirectional"))
      (node (ref "U$1") (pin "P$K2") (pinfunction "P0.05/AIN3_P$K2") (pintype "bidirectional"))
    )
    (net (code "16") (name "EPD_DC") (class "Default")
      (node (ref "J3") (pin "11") (pinfunction "11_11") (pintype "bidirectional"))
      (node (ref "U$1") (pin "P$AD10") (pinfunction "P0.15_P$AD10") (pintype "bidirectional"))
    )
    (net (code "17") (name "EPD_RST") (class "Default")
      (node (ref "J3") (pin "10") (pinfunction "10_10") (pintype "bidirectional"))
      (node (ref "U$1") (pin "P$AC11") (pinfunction "P0.16_P$AC11") (pintype "bidirectional"))
    )
    (net (code "18") (name "GDR") (class "Default")
      (node (ref "J3") (pin "2") (pinfunction "2_2") (pintype "bidirectional"))
      (node (ref "Q1") (pin "1") (pinfunction "G_1") (pintype "bidirectional"))
      (node (ref "R8") (pin "2") (pinfunction "2_2") (pintype "bidirectional"))
    )
    (net (code "19") (name "GND") (class "Default")
      (node (ref "C1") (pin "2") (pinfunction "2_2") (pintype "passive"))
      (node (ref "C1-EP-DR") (pin "2") (pinfunction "2_2") (pintype "passive"))
      (node (ref "C10") (pin "2") (pinfunction "2_2") (pintype "passive"))
      (node (ref "C11") (pin "2") (pinfunction "2_2") (pintype "passive"))
      (node (ref "C12") (pin "2") (pinfunction "2_2") (pintype "passive"))
      (node (ref "C13") (pin "2") (pinfunction "2_2") (pintype "passive"))
      (node (ref "C14") (pin "2") (pinfunction "2_2") (pintype "passive"))
      (node (ref "C15") (pin "2") (pinfunction "2_2") (pintype "passive"))
      (node (ref "C16") (pin "2") (pinfunction "2_2") (pintype "passive"))
      (node (ref "C17") (pin "1") (pinfunction "1_1") (pintype "passive"))
      (node (ref "C18") (pin "1") (pinfunction "1_1") (pintype "passive"))
      (node (ref "C19") (pin "2") (pinfunction "2_2") (pintype "passive"))
      (node (ref "C2") (pin "2") (pinfunction "2_2") (pintype "passive"))
      (node (ref "C20") (pin "2") (pinfunction "2_2") (pintype "passive"))
      (node (ref "C21") (pin "2") (pinfunction "2_2") (pintype "passive"))
      (node (ref "C22") (pin "2") (pinfunction "2_2") (pintype "passive"))
      (node (ref "C23") (pin "2") (pinfunction "2_2") (pintype "passive"))
      (node (ref "C24") (pin "2") (pinfunction "2_2") (pintype "passive"))
      (node (ref "C25") (pin "2") (pinfunction "2_2") (pintype "passive"))
      (node (ref "C26") (pin "2") (pinfunction "2_2") (pintype "passive"))
      (node (ref "C27") (pin "2") (pinfunction "2_2") (pintype "passive"))
      (node (ref "C28") (pin "2") (pinfunction "2_2") (pintype "passive"))
      (node (ref "C29") (pin "2") (pinfunction "2_2") (pintype "passive"))
      (node (ref "C3") (pin "2") (pinfunction "2_2") (pintype "passive"))
      (node (ref "C30") (pin "1") (pinfunction "1_1") (pintype "passive"))
      (node (ref "C31") (pin "1") (pinfunction "1_1") (pintype "passive"))
      (node (ref "C32") (pin "1") (pinfunction "1_1") (pintype "passive"))
      (node (ref "C33") (pin "2") (pinfunction "2_2") (pintype "passive"))
      (node (ref "C34") (pin "1") (pinfunction "1_1") (pintype "passive"))
      (node (ref "C35") (pin "1") (pinfunction "1_1") (pintype "passive"))
      (node (ref "C36") (pin "1") (pinfunction "1_1") (pintype "passive"))
      (node (ref "C37") (pin "2") (pinfunction "2_2") (pintype "passive"))
      (node (ref "C38") (pin "2") (pinfunction "2_2") (pintype "passive"))
      (node (ref "C39") (pin "2") (pinfunction "2_2") (pintype "passive"))
      (node (ref "C4") (pin "2") (pinfunction "2_2") (pintype "passive"))
      (node (ref "C40") (pin "1") (pinfunction "1_1") (pintype "passive"))
      (node (ref "C41") (pin "1") (pinfunction "1_1") (pintype "passive"))
      (node (ref "C42") (pin "1") (pinfunction "1_1") (pintype "passive"))
      (node (ref "C43") (pin "1") (pinfunction "1_1") (pintype "passive"))
      (node (ref "C44") (pin "1") (pinfunction "1_1") (pintype "passive"))
      (node (ref "C5") (pin "2") (pinfunction "2_2") (pintype "passive"))
      (node (ref "C6") (pin "2") (pinfunction "2_2") (pintype "passive"))
      (node (ref "C7") (pin "2") (pinfunction "2_2") (pintype "passive"))
      (node (ref "C8") (pin "2") (pinfunction "2_2") (pintype "passive"))
      (node (ref "C9") (pin "2") (pinfunction "2_2") (pintype "passive"))
      (node (ref "D3") (pin "1") (pinfunction "K_1") (pintype "bidirectional"))
      (node (ref "D4") (pin "2") (pinfunction "GND_2") (pintype "bidirectional"))
      (node (ref "IC1") (pin "8") (pinfunction "GNDIO_8") (pintype "bidirectional"))
      (node (ref "IC1") (pin "9") (pinfunction "GND_9") (pintype "bidirectional"))
      (node (ref "IC2") (pin "B1") (pinfunction "VSEL_B1") (pintype "bidirectional"))
      (node (ref "IC2") (pin "C1") (pinfunction "AGND_C1") (pintype "bidirectional"))
      (node (ref "IC2") (pin "C2") (pinfunction "PGND_1_C2") (pintype "bidirectional"))
      (node (ref "IC2") (pin "C3") (pinfunction "PGND_2_C3") (pintype "bidirectional"))
      (node (ref "IC3") (pin "D2") (pinfunction "GND_D2") (pintype "bidirectional"))
      (node (ref "IC4") (pin "B1") (pinfunction "IN/TRIG_B1") (pintype "bidirectional"))
      (node (ref "IC4") (pin "B3") (pinfunction "GND_B3") (pintype "bidirectional"))
      (node (ref "J1") (pin "3") (pinfunction "3_3") (pintype "bidirectional"))
      (node (ref "J1") (pin "5") (pinfunction "5_5") (pintype "bidirectional"))
      (node (ref "J2") (pin "A12_B1") (pinfunction "GND_A12_B1") (pintype "power_in"))
      (node (ref "J2") (pin "A1_B12") (pinfunction "GND_A1_B12") (pintype "power_in"))
      (node (ref "J2") (pin "SH1") (pinfunction "SHIELD_SH1") (pintype "passive"))
      (node (ref "J2") (pin "SH2") (pinfunction "SHIELD_SH2") (pintype "passive"))
      (node (ref "J2") (pin "SH3") (pinfunction "SHIELD_SH3") (pintype "passive"))
      (node (ref "J2") (pin "SH4") (pinfunction "SHIELD_SH4") (pintype "passive"))
      (node (ref "J3") (pin "17") (pinfunction "17_17") (pintype "bidirectional"))
      (node (ref "J3") (pin "8") (pinfunction "8_8") (pintype "bidirectional"))
      (node (ref "J3") (pin "MP1") (pinfunction "MP1_MP1") (pintype "bidirectional"))
      (node (ref "J3") (pin "MP2") (pinfunction "MP2_MP2") (pintype "bidirectional"))
      (node (ref "R13") (pin "1") (pinfunction "1_1") (pintype "bidirectional"))
      (node (ref "R14") (pin "2") (pinfunction "2_2") (pintype "bidirectional"))
      (node (ref "R3") (pin "1") (pinfunction "1_1") (pintype "bidirectional"))
      (node (ref "R7") (pin "1") (pinfunction "1_1") (pintype "bidirectional"))
      (node (ref "R8") (pin "1") (pinfunction "1_1") (pintype "bidirectional"))
      (node (ref "R9") (pin "1") (pinfunction "1_1") (pintype "bidirectional"))
      (node (ref "SJ1") (pin "1") (pinfunction "1_1") (pintype "passive"))
      (node (ref "SW1") (pin "1") (pinfunction "1_1") (pintype "passive"))
      (node (ref "SW2") (pin "1") (pinfunction "1_1") (pintype "passive"))
      (node (ref "SW3") (pin "1") (pinfunction "1_1") (pintype "passive"))
      (node (ref "TP6") (pin "TP") (pinfunction "TP_TP") (pintype "input"))
      (node (ref "TP_BAT_GND") (pin "TP") (pinfunction "TP_TP") (pintype "input"))
      (node (ref "U$1") (pin "P$74") (pinfunction "VSS_PAD_P$74") (pintype "bidirectional"))
      (node (ref "U$1") (pin "P$75") (pinfunction "VSS_PAD_P$75") (pintype "bidirectional"))
      (node (ref "U$1") (pin "P$76") (pinfunction "VSS_PAD_P$76") (pintype "bidirectional"))
      (node (ref "U$1") (pin "P$77") (pinfunction "VSS_PAD_P$77") (pintype "bidirectional"))
      (node (ref "U$1") (pin "P$78") (pinfunction "VSS_PAD_P$78") (pintype "bidirectional"))
      (node (ref "U$1") (pin "P$79") (pinfunction "VSS_PAD_P$79") (pintype "bidirectional"))
      (node (ref "U$1") (pin "P$80") (pinfunction "VSS_PAD_P$80") (pintype "bidirectional"))
      (node (ref "U$1") (pin "P$81") (pinfunction "VSS_PAD_P$81") (pintype "bidirectional"))
      (node (ref "U$1") (pin "P$82") (pinfunction "VSS_PAD_P$82") (pintype "bidirectional"))
      (node (ref "U$1") (pin "P$83") (pinfunction "VSS_PAD_P$83") (pintype "bidirectional"))
      (node (ref "U$1") (pin "P$84") (pinfunction "VSS_PAD_P$84") (pintype "bidirectional"))
      (node (ref "U$1") (pin "P$85") (pinfunction "VSS_PAD_P$85") (pintype "bidirectional"))
      (node (ref "U$1") (pin "P$86") (pinfunction "VSS_PAD_P$86") (pintype "bidirectional"))
      (node (ref "U$1") (pin "P$87") (pinfunction "VSS_PAD_P$87") (pintype "bidirectional"))
      (node (ref "U$1") (pin "P$88") (pinfunction "VSS_PAD_P$88") (pintype "bidirectional"))
      (node (ref "U$1") (pin "P$89") (pinfunction "VSS_PAD_P$89") (pintype "bidirectional"))
      (node (ref "U$1") (pin "P$90") (pinfunction "VSS_PAD_P$90") (pintype "bidirectional"))
      (node (ref "U$1") (pin "P$B7") (pinfunction "VSS_P$B7") (pintype "power_in"))
      (node (ref "U$1") (pin "P$F23") (pinfunction "VSS_PA_P$F23") (pintype "bidirectional"))
      (node (ref "U$3") (pin "1") (pinfunction "1_1") (pintype "passive"))
      (node (ref "U$4") (pin "2") (pinfunction "2_2") (pintype "passive"))
      (node (ref "U$5") (pin "2") (pinfunction "2_2") (pintype "passive"))
      (node (ref "U1") (pin "1") (pinfunction "CTG_1") (pintype "power_in"))
      (node (ref "U1") (pin "4") (pinfunction "GND_4") (pintype "power_in"))
      (node (ref "U1") (pin "6") (pinfunction "QSTRT_6") (pintype "input"))
      (node (ref "U1") (pin "9") (pinfunction "EP_9") (pintype "power_in"))
      (node (ref "X1") (pin "2") (pinfunction "2_2") (pintype "passive"))
      (node (ref "X1") (pin "4") (pinfunction "4_4") (pintype "passive"))
    )
    (net (code "20") (name "HAPTIC_EN") (class "Default")
      (node (ref "IC4") (pin "A1") (pinfunction "EN_A1") (pintype "bidirectional"))
      (node (ref "U$1") (pin "P$U1") (pinfunction "P0.12_P$U1") (pintype "bidirectional"))
    )
    (net (code "21") (name "IMU_INT1") (class "Default")
      (node (ref "IC1") (pin "5") (pinfunction "INT1_5") (pintype "bidirectional"))
      (node (ref "U$1") (pin "P$N1") (pinfunction "P0.08_P$N1") (pintype "bidirectional"))
    )
    (net (code "22") (name "IMU_INT2") (class "Default")
      (node (ref "IC1") (pin "6") (pinfunction "INT2_6") (pintype "bidirectional"))
      (node (ref "U$1") (pin "P$P2") (pinfunction "P1.08_P$P2") (pintype "bidirectional"))
    )
    (net (code "23") (name "LX1") (class "Default")
      (node (ref "IC2") (pin "B2") (pinfunction "SW1_1_B2") (pintype "bidirectional"))
      (node (ref "IC2") (pin "B3") (pinfunction "SW1_2_B3") (pintype "bidirectional"))
      (node (ref "L1") (pin "1") (pinfunction "1_1") (pintype "bidirectional"))
    )
    (net (code "24") (name "LX2") (class "Default")
      (node (ref "IC2") (pin "D2") (pinfunction "SW2_1_D2") (pintype "bidirectional"))
      (node (ref "IC2") (pin "D3") (pinfunction "SW2_2_D3") (pintype "bidirectional"))
      (node (ref "L1") (pin "2") (pinfunction "2_2") (pintype "bidirectional"))
    )
    (net (code "25") (name "MOSI") (class "Default")
      (node (ref "J3") (pin "14") (pinfunction "14_14") (pintype "bidirectional"))
      (node (ref "U$1") (pin "P$B13") (pinfunction "P0.03/AIN1_P$B13") (pintype "bidirectional"))
    )
    (net (code "26") (name "Net-(ANT1-FEED)") (class "Default")
      (node (ref "ANT1") (pin "1") (pinfunction "FEED_1") (pintype "input"))
      (node (ref "C1") (pin "1") (pinfunction "1_1") (pintype "passive"))
      (node (ref "C22") (pin "1") (pinfunction "1_1") (pintype "passive"))
      (node (ref "U$2") (pin "2") (pinfunction "2_2") (pintype "passive"))
    )
    (net (code "27") (name "Net-(C32-Pad2)") (class "Default")
      (node (ref "C32") (pin "2") (pinfunction "2_2") (pintype "passive"))
      (node (ref "J3") (pin "18") (pinfunction "18_18") (pintype "bidirectional"))
    )
    (net (code "28") (name "Net-(C34-Pad2)") (class "Default")
      (node (ref "C34") (pin "2") (pinfunction "2_2") (pintype "passive"))
      (node (ref "J3") (pin "19") (pinfunction "19_19") (pintype "bidirectional"))
    )
    (net (code "29") (name "Net-(C35-Pad2)") (class "Default")
      (node (ref "C35") (pin "2") (pinfunction "2_2") (pintype "passive"))
      (node (ref "J3") (pin "20") (pinfunction "20_20") (pintype "bidirectional"))
    )
    (net (code "30") (name "Net-(C41-Pad2)") (class "Default")
      (node (ref "C41") (pin "2") (pinfunction "2_2") (pintype "passive"))
      (node (ref "J3") (pin "23") (pinfunction "23_23") (pintype "bidirectional"))
    )
    (net (code "31") (name "Net-(C42-Pad2)") (class "Default")
      (node (ref "C42") (pin "2") (pinfunction "2_2") (pintype "passive"))
      (node (ref "J3") (pin "24") (pinfunction "24_24") (pintype "bidirectional"))
    )
    (net (code "32") (name "Net-(C43-Pad2)") (class "Default")
      (node (ref "C43") (pin "2") (pinfunction "2_2") (pintype "passive"))
      (node (ref "J3") (pin "4") (pinfunction "4_4") (pintype "bidirectional"))
    )
    (net (code "33") (name "Net-(C44-Pad2)") (class "Default")
      (node (ref "C44") (pin "2") (pinfunction "2_2") (pintype "passive"))
      (node (ref "J3") (pin "5") (pinfunction "5_5") (pintype "bidirectional"))
    )
    (net (code "34") (name "Net-(D1-A)") (class "Default")
      (node (ref "C1-EP-DR1") (pin "2") (pinfunction "2_2") (pintype "passive"))
      (node (ref "D1") (pin "2") (pinfunction "A_2") (pintype "bidirectional"))
      (node (ref "L5") (pin "2") (pinfunction "2_2") (pintype "passive"))
    )
    (net (code "35") (name "Net-(D2-K)") (class "Default")
      (node (ref "C1-EP-DR1") (pin "1") (pinfunction "1_1") (pintype "passive"))
      (node (ref "D2") (pin "1") (pinfunction "K_1") (pintype "bidirectional"))
      (node (ref "D3") (pin "2") (pinfunction "A_2") (pintype "bidirectional"))
      (node (ref "Q1") (pin "3") (pinfunction "D_3") (pintype "bidirectional"))
    )
    (net (code "36") (name "Net-(IC1-SDO)") (class "Default")
      (node (ref "IC1") (pin "1") (pinfunction "SDO_1") (pintype "bidirectional"))
      (node (ref "R3") (pin "2") (pinfunction "2_2") (pintype "bidirectional"))
    )
    (net (code "37") (name "Net-(IC2-SCL)") (class "Default")
      (node (ref "IC2") (pin "D1") (pinfunction "SCL_D1") (pintype "bidirectional"))
      (node (ref "R2") (pin "2") (pinfunction "2_2") (pintype "bidirectional"))
    )
    (net (code "38") (name "Net-(IC2-SDA)") (class "Default")
      (node (ref "IC2") (pin "E1") (pinfunction "SDA_E1") (pintype "bidirectional"))
      (node (ref "R1") (pin "2") (pinfunction "2_2") (pintype "bidirectional"))
    )
    (net (code "39") (name "Net-(IC3-TS{slash}MR)") (class "Default")
      (node (ref "IC3") (pin "D1") (pinfunction "TS/MR_D1") (pintype "bidirectional"))
      (node (ref "R9") (pin "2") (pinfunction "2_2") (pintype "bidirectional"))
    )
    (net (code "40") (name "Net-(IC4-REG)") (class "Default")
      (node (ref "C4") (pin "1") (pinfunction "1_1") (pintype "passive"))
      (node (ref "IC4") (pin "A2") (pinfunction "REG_A2") (pintype "bidirectional"))
    )
    (net (code "41") (name "Net-(J2-CC1)") (class "Default")
      (node (ref "J2") (pin "A5") (pinfunction "CC1_A5") (pintype "bidirectional"))
      (node (ref "R13") (pin "2") (pinfunction "2_2") (pintype "bidirectional"))
    )
    (net (code "42") (name "Net-(J2-CC2)") (class "Default")
      (node (ref "J2") (pin "B5") (pinfunction "CC2_B5") (pintype "bidirectional"))
      (node (ref "R14") (pin "1") (pinfunction "1_1") (pintype "bidirectional"))
    )
    (net (code "43") (name "Net-(L2-Pad2)") (class "Default")
      (node (ref "L2") (pin "2") (pinfunction "2_2") (pintype "passive"))
      (node (ref "L3") (pin "1") (pinfunction "1_1") (pintype "passive"))
    )
    (net (code "44") (name "Net-(R6-Pad1)") (class "Default")
      (node (ref "R6") (pin "1") (pinfunction "1_1") (pintype "bidirectional"))
      (node (ref "R7") (pin "2") (pinfunction "2_2") (pintype "bidirectional"))
      (node (ref "SJ1") (pin "2") (pinfunction "2_2") (pintype "passive"))
    )
    (net (code "45") (name "Net-(U$1-ANT)") (class "Default")
      (node (ref "C3") (pin "1") (pinfunction "1_1") (pintype "passive"))
      (node (ref "U$1") (pin "P$H23") (pinfunction "ANT_P$H23") (pintype "bidirectional"))
      (node (ref "U$2") (pin "1") (pinfunction "1_1") (pintype "passive"))
    )
    (net (code "46") (name "Net-(U$1-DCC)") (class "Default")
      (node (ref "L2") (pin "1") (pinfunction "1_1") (pintype "passive"))
      (node (ref "U$1") (pin "P$B3") (pinfunction "DCC_P$B3") (pintype "output"))
    )
    (net (code "47") (name "Net-(U$1-DEC1)") (class "Default")
      (node (ref "C5") (pin "1") (pinfunction "1_1") (pintype "passive"))
      (node (ref "U$1") (pin "P$C1") (pinfunction "DEC1_P$C1") (pintype "power_in"))
    )
    (net (code "48") (name "Net-(U$1-DEC3V3)") (class "Default")
      (node (ref "C20") (pin "1") (pinfunction "1_1") (pintype "passive"))
      (node (ref "U$1") (pin "P$AC5") (pinfunction "DEC3V3_P$AC5") (pintype "bidirectional"))
    )
    (net (code "49") (name "Net-(U$1-DEC5)") (class "Default")
      (node (ref "C9") (pin "1") (pinfunction "1_1") (pintype "passive"))
      (node (ref "U$1") (pin "P$N24") (pinfunction "DEC5_P$N24") (pintype "bidirectional"))
    )
    (net (code "50") (name "Net-(U$1-XC1)") (class "Default")
      (node (ref "U$1") (pin "P$B24") (pinfunction "XC1_P$B24") (pintype "input"))
      (node (ref "U$4") (pin "1") (pinfunction "1_1") (pintype "passive"))
      (node (ref "X1") (pin "1") (pinfunction "1_1") (pintype "passive"))
    )
    (net (code "51") (name "Net-(U$1-XC2)") (class "Default")
      (node (ref "U$1") (pin "P$A23") (pinfunction "XC2_P$A23") (pintype "output"))
      (node (ref "U$5") (pin "1") (pinfunction "1_1") (pintype "passive"))
      (node (ref "X1") (pin "3") (pinfunction "3_3") (pintype "passive"))
    )
    (net (code "52") (name "OUT+") (class "Default")
      (node (ref "IC4") (pin "A3") (pinfunction "OUT+_A3") (pintype "bidirectional"))
      (node (ref "TP_OP") (pin "TP") (pinfunction "TP_TP") (pintype "input"))
    )
    (net (code "53") (name "OUT-") (class "Default")
      (node (ref "IC4") (pin "C3") (pinfunction "OUT-_C3") (pintype "bidirectional"))
      (node (ref "TP_ON") (pin "TP") (pinfunction "TP_TP") (pintype "input"))
    )
    (net (code "54") (name "P0.04") (class "Default")
      (node (ref "U$1") (pin "P$J1") (pinfunction "P0.04/AIN2_P$J1") (pintype "bidirectional"))
    )
    (net (code "55") (name "P0.09") (class "Default")
      (node (ref "U$1") (pin "P$L24") (pinfunction "P0.09/NFC1_P$L24") (pintype "bidirectional"))
    )
    (net (code "56") (name "P0.13{slash}1.5D") (class "Default")
      (node (ref "C27") (pin "1") (pinfunction "1_1") (pintype "passive"))
      (node (ref "R10") (pin "1") (pinfunction "1_1") (pintype "bidirectional"))
      (node (ref "SW1") (pin "2") (pinfunction "2_2") (pintype "passive"))
    )
    (net (code "57") (name "P0.13{slash}2.6C") (class "Default")
      (node (ref "U$1") (pin "P$AD8") (pinfunction "P0.13_P$AD8") (pintype "bidirectional"))
    )
    (net (code "58") (name "P0.14{slash}1.5D") (class "Default")
      (node (ref "C28") (pin "1") (pinfunction "1_1") (pintype "passive"))
      (node (ref "R11") (pin "1") (pinfunction "1_1") (pintype "bidirectional"))
      (node (ref "SW2") (pin "2") (pinfunction "2_2") (pintype "passive"))
    )
    (net (code "59") (name "P0.14{slash}2.7C") (class "Default")
      (node (ref "U$1") (pin "P$AC9") (pinfunction "P0.14_P$AC9") (pintype "bidirectional"))
    )
    (net (code "60") (name "P0.19") (class "Default")
      (node (ref "U$1") (pin "P$AC15") (pinfunction "P0.19_P$AC15") (pintype "bidirectional"))
    )
    (net (code "61") (name "P0.20") (class "Default")
      (node (ref "U$1") (pin "P$AD16") (pinfunction "P0.20_P$AD16") (pintype "bidirectional"))
    )
    (net (code "62") (name "P0.21") (class "Default")
      (node (ref "U$1") (pin "P$AC17") (pinfunction "P0.21_P$AC17") (pintype "bidirectional"))
    )
    (net (code "63") (name "P0.22") (class "Default")
      (node (ref "U$1") (pin "P$AD18") (pinfunction "P0.22_P$AD18") (pintype "bidirectional"))
    )
    (net (code "64") (name "P0.23") (class "Default")
      (node (ref "U$1") (pin "P$AC19") (pinfunction "P0.23_P$AC19") (pintype "bidirectional"))
    )
    (net (code "65") (name "P0.24") (class "Default")
      (node (ref "U$1") (pin "P$AD20") (pinfunction "P0.24_P$AD20") (pintype "bidirectional"))
    )
    (net (code "66") (name "P0.25") (class "Default")
      (node (ref "U$1") (pin "P$AC21") (pinfunction "P0.25_P$AC21") (pintype "bidirectional"))
    )
    (net (code "67") (name "P0.26") (class "Default")
      (node (ref "U$1") (pin "P$G1") (pinfunction "P0.26_P$G1") (pintype "bidirectional"))
    )
    (net (code "68") (name "P0.27") (class "Default")
      (node (ref "U$1") (pin "P$H2") (pinfunction "P0.27_P$H2") (pintype "bidirectional"))
    )
    (net (code "69") (name "P0.28") (class "Default")
      (node (ref "U$1") (pin "P$B11") (pinfunction "P0.28/AIN4_P$B11") (pintype "bidirectional"))
    )
    (net (code "70") (name "P0.29") (class "Default")
      (node (ref "U$1") (pin "P$A10") (pinfunction "P0.29/AIN5_P$A10") (pintype "bidirectional"))
    )
    (net (code "71") (name "P0.30") (class "Default")
      (node (ref "U$1") (pin "P$B9") (pinfunction "P0.30/AIN6_P$B9") (pintype "bidirectional"))
    )
    (net (code "72") (name "P0.31") (class "Default")
      (node (ref "U$1") (pin "P$A8") (pinfunction "P0.31/AIN7_P$A8") (pintype "bidirectional"))
    )
    (net (code "73") (name "P1.01{slash}1.6C") (class "Default")
      (node (ref "Q2") (pin "1") (pinfunction "G_1") (pintype "bidirectional"))
      (node (ref "R16") (pin "1") (pinfunction "1_1") (pintype "bidirectional"))
    )
    (net (code "74") (name "P1.01{slash}2.4B") (class "Default")
      (node (ref "U$1") (pin "P$Y23") (pinfunction "P1.01_P$Y23") (pintype "bidirectional"))
    )
    (net (code "75") (name "P1.01{slash}2.4C") (class "Default")
      (node (ref "U$1") (pin "P$W24") (pinfunction "P1.02_P$W24") (pintype "bidirectional"))
    )
    (net (code "76") (name "P1.02{slash}1.6C") (class "Default")
      (node (ref "C29") (pin "1") (pinfunction "1_1") (pintype "passive"))
      (node (ref "R12") (pin "1") (pinfunction "1_1") (pintype "bidirectional"))
      (node (ref "SW3") (pin "2") (pinfunction "2_2") (pintype "passive"))
    )
    (net (code "77") (name "P1.03") (class "Default")
      (node (ref "U$1") (pin "P$V23") (pinfunction "P1.03_P$V23") (pintype "bidirectional"))
    )
    (net (code "78") (name "P1.04") (class "Default")
      (node (ref "U$1") (pin "P$U24") (pinfunction "P1.04_P$U24") (pintype "bidirectional"))
    )
    (net (code "79") (name "P1.05") (class "Default")
      (node (ref "U$1") (pin "P$T23") (pinfunction "P1.05_P$T23") (pintype "bidirectional"))
    )
    (net (code "80") (name "P1.06") (class "Default")
      (node (ref "U$1") (pin "P$R24") (pinfunction "P1.06_P$R24") (pintype "bidirectional"))
    )
    (net (code "81") (name "P1.07") (class "Default")
      (node (ref "U$1") (pin "P$P23") (pinfunction "P1.07_P$P23") (pintype "bidirectional"))
    )
    (net (code "82") (name "P1.09") (class "Default")
      (node (ref "U$1") (pin "P$R1") (pinfunction "P1.09_P$R1") (pintype "bidirectional"))
    )
    (net (code "83") (name "P1.10") (class "Default")
      (node (ref "U$1") (pin "P$A20") (pinfunction "P1.10_P$A20") (pintype "bidirectional"))
    )
    (net (code "84") (name "P1.11") (class "Default")
      (node (ref "U$1") (pin "P$B19") (pinfunction "P1.11_P$B19") (pintype "bidirectional"))
    )
    (net (code "85") (name "P1.12") (class "Default")
      (node (ref "U$1") (pin "P$B17") (pinfunction "P1.12_P$B17") (pintype "bidirectional"))
    )
    (net (code "86") (name "P1.13") (class "Default")
      (node (ref "U$1") (pin "P$A16") (pinfunction "P1.13_P$A16") (pintype "bidirectional"))
    )
    (net (code "87") (name "P1.14") (class "Default")
      (node (ref "U$1") (pin "P$B15") (pinfunction "P1.14_P$B15") (pintype "bidirectional"))
    )
    (net (code "88") (name "P1.15") (class "Default")
      (node (ref "U$1") (pin "P$A14") (pinfunction "P1.15_P$A14") (pintype "bidirectional"))
    )
    (net (code "89") (name "PMIC_INT") (class "Default")
      (node (ref "IC3") (pin "A1") (pinfunction "~{INT}_A1") (pintype "bidirectional"))
      (node (ref "U$1") (pin "P$T2") (pinfunction "P0.11_P$T2") (pintype "bidirectional"))
    )
    (net (code "90") (name "PREVGH") (class "Default")
      (node (ref "C36") (pin "2") (pinfunction "2_2") (pintype "passive"))
      (node (ref "D1") (pin "1") (pinfunction "K_1") (pintype "bidirectional"))
      (node (ref "J3") (pin "21") (pinfunction "21_21") (pintype "bidirectional"))
    )
    (net (code "91") (name "PREVGL") (class "Default")
      (node (ref "C40") (pin "2") (pinfunction "2_2") (pintype "passive"))
      (node (ref "D2") (pin "2") (pinfunction "A_2") (pintype "bidirectional"))
      (node (ref "J3") (pin "22") (pinfunction "22_22") (pintype "bidirectional"))
    )
    (net (code "92") (name "RESE") (class "Default")
      (node (ref "J3") (pin "3") (pinfunction "3_3") (pintype "bidirectional"))
      (node (ref "Q1") (pin "2") (pinfunction "S_2") (pintype "bidirectional"))
      (node (ref "R6") (pin "2") (pinfunction "2_2") (pintype "bidirectional"))
    )
    (net (code "93") (name "RESET") (class "Default")
      (node (ref "J1") (pin "6") (pinfunction "6_6") (pintype "bidirectional"))
      (node (ref "TP2") (pin "TP") (pinfunction "TP_TP") (pintype "input"))
      (node (ref "U$1") (pin "P$AC13") (pinfunction "P0.18/RESET_P$AC13") (pintype "bidirectional"))
    )
    (net (code "94") (name "SCK") (class "Default")
      (node (ref "J3") (pin "13") (pinfunction "13_13") (pintype "bidirectional"))
      (node (ref "U$1") (pin "P$A12") (pinfunction "P0.02/AIN0_P$A12") (pintype "bidirectional"))
    )
    (net (code "95") (name "SCL{slash}1.4C") (class "Default")
      (node (ref "IC4") (pin "C1") (pinfunction "SCL_C1") (pintype "bidirectional"))
      (node (ref "U1") (pin "7") (pinfunction "SCL_7") (pintype "input"))
    )
    (net (code "96") (name "SCL{slash}2.4C") (class "Default")
      (node (ref "IC1") (pin "12") (pinfunction "SCX_12") (pintype "bidirectional"))
      (node (ref "IC3") (pin "B1") (pinfunction "SCL_B1") (pintype "bidirectional"))
      (node (ref "R2") (pin "1") (pinfunction "1_1") (pintype "bidirectional"))
      (node (ref "R4") (pin "2") (pinfunction "2_2") (pintype "bidirectional"))
      (node (ref "TP_SCL") (pin "TP") (pinfunction "TP_TP") (pintype "input"))
      (node (ref "U$1") (pin "P$M2") (pinfunction "P0.07_P$M2") (pintype "bidirectional"))
    )
    (net (code "97") (name "SDA{slash}1.4C") (class "Default")
      (node (ref "IC4") (pin "B2") (pinfunction "SDA_B2") (pintype "bidirectional"))
      (node (ref "U1") (pin "8") (pinfunction "SDA_8") (pintype "bidirectional"))
    )
    (net (code "98") (name "SDA{slash}2.4C") (class "Default")
      (node (ref "IC1") (pin "2") (pinfunction "SDX_2") (pintype "bidirectional"))
      (node (ref "IC3") (pin "C1") (pinfunction "SDA_C1") (pintype "bidirectional"))
      (node (ref "R1") (pin "1") (pinfunction "1_1") (pintype "bidirectional"))
      (node (ref "R5") (pin "2") (pinfunction "2_2") (pintype "bidirectional"))
      (node (ref "TP_SDA") (pin "TP") (pinfunction "TP_TP") (pintype "input"))
      (node (ref "U$1") (pin "P$L1") (pinfunction "P0.06_P$L1") (pintype "bidirectional"))
    )
    (net (code "99") (name "SWDCLK") (class "Default")
      (node (ref "J1") (pin "4") (pinfunction "4_4") (pintype "bidirectional"))
      (node (ref "TP3") (pin "TP") (pinfunction "TP_TP") (pintype "input"))
      (node (ref "U$1") (pin "P$AA24") (pinfunction "SWDCLK_P$AA24") (pintype "input"))
    )
    (net (code "100") (name "SWDIO") (class "Default")
      (node (ref "J1") (pin "2") (pinfunction "2_2") (pintype "bidirectional"))
      (node (ref "TP4") (pin "TP") (pinfunction "TP_TP") (pintype "input"))
      (node (ref "U$1") (pin "P$AC24") (pinfunction "SWDIO_P$AC24") (pintype "bidirectional"))
    )
    (net (code "101") (name "SWO") (class "Default")
      (node (ref "TP_SWO") (pin "TP") (pinfunction "TP_TP") (pintype "input"))
      (node (ref "U$1") (pin "P$AD22") (pinfunction "P1.00_P$AD22") (pintype "bidirectional"))
    )
    (net (code "102") (name "VBAT") (class "Default")
      (node (ref "C26") (pin "1") (pinfunction "1_1") (pintype "passive"))
      (node (ref "C37") (pin "1") (pinfunction "1_1") (pintype "passive"))
      (node (ref "IC3") (pin "C2") (pinfunction "BAT_C2") (pintype "bidirectional"))
      (node (ref "TP_VBAT") (pin "TP") (pinfunction "TP_TP") (pintype "input"))
      (node (ref "U1") (pin "2") (pinfunction "CELL_2") (pintype "power_in"))
      (node (ref "U1") (pin "3") (pinfunction "VDD_3") (pintype "power_in"))
    )
    (net (code "103") (name "VBUS") (class "Default")
      (node (ref "C21") (pin "1") (pinfunction "1_1") (pintype "passive"))
      (node (ref "C30") (pin "2") (pinfunction "2_2") (pintype "passive"))
      (node (ref "C31") (pin "2") (pinfunction "2_2") (pintype "passive"))
      (node (ref "C38") (pin "1") (pinfunction "1_1") (pintype "passive"))
      (node (ref "D4") (pin "5") (pinfunction "VBUS_5") (pintype "bidirectional"))
      (node (ref "IC3") (pin "A2") (pinfunction "IN_A2") (pintype "bidirectional"))
      (node (ref "J2") (pin "A4_B9") (pinfunction "VBUS_A4_B9") (pintype "power_in"))
      (node (ref "J2") (pin "A9_B4") (pinfunction "VBUS_A9_B4") (pintype "power_in"))
      (node (ref "U$1") (pin "P$AD2") (pinfunction "VBUS_P$AD2") (pintype "power_in"))
    )
    (net (code "104") (name "VREG") (class "Default")
      (node (ref "C23") (pin "1") (pinfunction "1_1") (pintype "passive"))
      (node (ref "C24") (pin "1") (pinfunction "1_1") (pintype "passive"))
      (node (ref "C39") (pin "1") (pinfunction "1_1") (pintype "passive"))
      (node (ref "IC2") (pin "A1") (pinfunction "EN_A1") (pintype "bidirectional"))
      (node (ref "IC2") (pin "A2") (pinfunction "VIN_1_A2") (pintype "bidirectional"))
      (node (ref "IC2") (pin "A3") (pinfunction "VIN_2_A3") (pintype "bidirectional"))
      (node (ref "IC3") (pin "B2") (pinfunction "SYS_B2") (pintype "bidirectional"))
      (node (ref "TP7") (pin "TP") (pinfunction "TP_TP") (pintype "input"))
    )
    (net (code "105") (name "unconnected-(ANT1-NC-Pad2)") (class "Default")
      (node (ref "ANT1") (pin "2") (pinfunction "NC_2") (pintype "no_connect"))
    )
    (net (code "106") (name "unconnected-(IC1-ASCL-Pad11)") (class "Default")
      (node (ref "IC1") (pin "11") (pinfunction "ASCL_11") (pintype "bidirectional"))
    )
    (net (code "107") (name "unconnected-(IC1-ASDA-Pad4)") (class "Default")
      (node (ref "IC1") (pin "4") (pinfunction "ASDA_4") (pintype "bidirectional"))
    )
    (net (code "108") (name "unconnected-(IC2-VOUT_1-PadE2)") (class "Default")
      (node (ref "IC2") (pin "E2") (pinfunction "VOUT_1_E2") (pintype "bidirectional"))
    )
    (net (code "109") (name "unconnected-(J2-SBU1-PadA8)") (class "Default")
      (node (ref "J2") (pin "A8") (pinfunction "SBU1_A8") (pintype "bidirectional"))
    )
    (net (code "110") (name "unconnected-(J2-SBU2-PadB8)") (class "Default")
      (node (ref "J2") (pin "B8") (pinfunction "SBU2_B8") (pintype "bidirectional"))
    )
    (net (code "111") (name "unconnected-(J3-Pad1)") (class "Default")
      (node (ref "J3") (pin "1") (pinfunction "1_1") (pintype "bidirectional"))
    )
    (net (code "112") (name "unconnected-(J3-Pad6)") (class "Default")
      (node (ref "J3") (pin "6") (pinfunction "6_6") (pintype "bidirectional"))
    )
    (net (code "113") (name "unconnected-(J3-Pad7)") (class "Default")
      (node (ref "J3") (pin "7") (pinfunction "7_7") (pintype "bidirectional"))
    )
    (net (code "114") (name "unconnected-(U$1-DCCH-PadP$AB2)") (class "Default")
      (node (ref "U$1") (pin "P$AB2") (pinfunction "DCCH_P$AB2") (pintype "bidirectional"))
    )
  )
)
